# 5x18.net
KiCad netlist of a schematic drawn in EAGLE
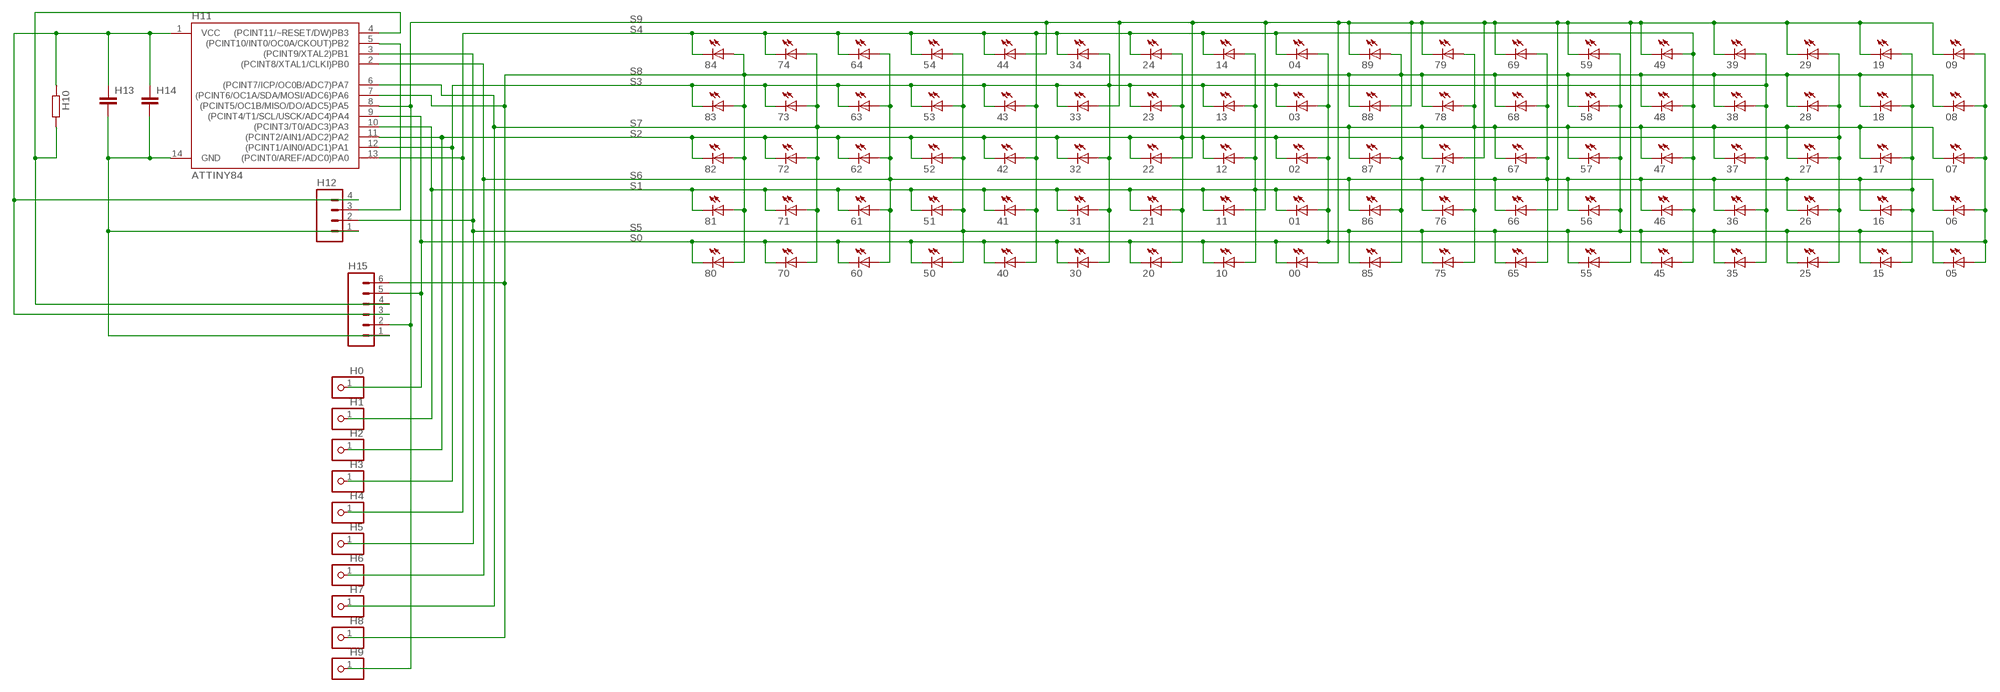
[diagram p0: schematic, sheet 1]

(export (version "E")
  (design (tool "Eeschema 10.0.6"))
  (components
    (comp (ref "00")
      (value "LED3MM")
      (footprint "eagle-import:LED3MM")
      (libsource (lib "eagle-import") (part "LED3MM"))
    )
    (comp (ref "01")
      (value "LED3MM")
      (footprint "eagle-import:LED3MM")
      (libsource (lib "eagle-import") (part "LED3MM"))
    )
    (comp (ref "02")
      (value "LED3MM")
      (footprint "eagle-import:LED3MM")
      (libsource (lib "eagle-import") (part "LED3MM"))
    )
    (comp (ref "03")
      (value "LED3MM")
      (footprint "eagle-import:LED3MM")
      (libsource (lib "eagle-import") (part "LED3MM"))
    )
    (comp (ref "04")
      (value "LED3MM")
      (footprint "eagle-import:LED3MM")
      (libsource (lib "eagle-import") (part "LED3MM"))
    )
    (comp (ref "05")
      (value "LED3MM")
      (footprint "eagle-import:LED3MM")
      (libsource (lib "eagle-import") (part "LED3MM"))
    )
    (comp (ref "06")
      (value "LED3MM")
      (footprint "eagle-import:LED3MM")
      (libsource (lib "eagle-import") (part "LED3MM"))
    )
    (comp (ref "07")
      (value "LED3MM")
      (footprint "eagle-import:LED3MM")
      (libsource (lib "eagle-import") (part "LED3MM"))
    )
    (comp (ref "08")
      (value "LED3MM")
      (footprint "eagle-import:LED3MM")
      (libsource (lib "eagle-import") (part "LED3MM"))
    )
    (comp (ref "09")
      (value "LED3MM")
      (footprint "eagle-import:LED3MM")
      (libsource (lib "eagle-import") (part "LED3MM"))
    )
    (comp (ref "10")
      (value "LED3MM")
      (footprint "eagle-import:LED3MM")
      (libsource (lib "eagle-import") (part "LED3MM"))
    )
    (comp (ref "11")
      (value "LED3MM")
      (footprint "eagle-import:LED3MM")
      (libsource (lib "eagle-import") (part "LED3MM"))
    )
    (comp (ref "12")
      (value "LED3MM")
      (footprint "eagle-import:LED3MM")
      (libsource (lib "eagle-import") (part "LED3MM"))
    )
    (comp (ref "13")
      (value "LED3MM")
      (footprint "eagle-import:LED3MM")
      (libsource (lib "eagle-import") (part "LED3MM"))
    )
    (comp (ref "14")
      (value "LED3MM")
      (footprint "eagle-import:LED3MM")
      (libsource (lib "eagle-import") (part "LED3MM"))
    )
    (comp (ref "15")
      (value "LED3MM")
      (footprint "eagle-import:LED3MM")
      (libsource (lib "eagle-import") (part "LED3MM"))
    )
    (comp (ref "16")
      (value "LED3MM")
      (footprint "eagle-import:LED3MM")
      (libsource (lib "eagle-import") (part "LED3MM"))
    )
    (comp (ref "17")
      (value "LED3MM")
      (footprint "eagle-import:LED3MM")
      (libsource (lib "eagle-import") (part "LED3MM"))
    )
    (comp (ref "18")
      (value "LED3MM")
      (footprint "eagle-import:LED3MM")
      (libsource (lib "eagle-import") (part "LED3MM"))
    )
    (comp (ref "19")
      (value "LED3MM")
      (footprint "eagle-import:LED3MM")
      (libsource (lib "eagle-import") (part "LED3MM"))
    )
    (comp (ref "20")
      (value "LED3MM")
      (footprint "eagle-import:LED3MM")
      (libsource (lib "eagle-import") (part "LED3MM"))
    )
    (comp (ref "21")
      (value "LED3MM")
      (footprint "eagle-import:LED3MM")
      (libsource (lib "eagle-import") (part "LED3MM"))
    )
    (comp (ref "22")
      (value "LED3MM")
      (footprint "eagle-import:LED3MM")
      (libsource (lib "eagle-import") (part "LED3MM"))
    )
    (comp (ref "23")
      (value "LED3MM")
      (footprint "eagle-import:LED3MM")
      (libsource (lib "eagle-import") (part "LED3MM"))
    )
    (comp (ref "24")
      (value "LED3MM")
      (footprint "eagle-import:LED3MM")
      (libsource (lib "eagle-import") (part "LED3MM"))
    )
    (comp (ref "25")
      (value "LED3MM")
      (footprint "eagle-import:LED3MM")
      (libsource (lib "eagle-import") (part "LED3MM"))
    )
    (comp (ref "26")
      (value "LED3MM")
      (footprint "eagle-import:LED3MM")
      (libsource (lib "eagle-import") (part "LED3MM"))
    )
    (comp (ref "27")
      (value "LED3MM")
      (footprint "eagle-import:LED3MM")
      (libsource (lib "eagle-import") (part "LED3MM"))
    )
    (comp (ref "28")
      (value "LED3MM")
      (footprint "eagle-import:LED3MM")
      (libsource (lib "eagle-import") (part "LED3MM"))
    )
    (comp (ref "29")
      (value "LED3MM")
      (footprint "eagle-import:LED3MM")
      (libsource (lib "eagle-import") (part "LED3MM"))
    )
    (comp (ref "30")
      (value "LED3MM")
      (footprint "eagle-import:LED3MM")
      (libsource (lib "eagle-import") (part "LED3MM"))
    )
    (comp (ref "31")
      (value "LED3MM")
      (footprint "eagle-import:LED3MM")
      (libsource (lib "eagle-import") (part "LED3MM"))
    )
    (comp (ref "32")
      (value "LED3MM")
      (footprint "eagle-import:LED3MM")
      (libsource (lib "eagle-import") (part "LED3MM"))
    )
    (comp (ref "33")
      (value "LED3MM")
      (footprint "eagle-import:LED3MM")
      (libsource (lib "eagle-import") (part "LED3MM"))
    )
    (comp (ref "34")
      (value "LED3MM")
      (footprint "eagle-import:LED3MM")
      (libsource (lib "eagle-import") (part "LED3MM"))
    )
    (comp (ref "35")
      (value "LED3MM")
      (footprint "eagle-import:LED3MM")
      (libsource (lib "eagle-import") (part "LED3MM"))
    )
    (comp (ref "36")
      (value "LED3MM")
      (footprint "eagle-import:LED3MM")
      (libsource (lib "eagle-import") (part "LED3MM"))
    )
    (comp (ref "37")
      (value "LED3MM")
      (footprint "eagle-import:LED3MM")
      (libsource (lib "eagle-import") (part "LED3MM"))
    )
    (comp (ref "38")
      (value "LED3MM")
      (footprint "eagle-import:LED3MM")
      (libsource (lib "eagle-import") (part "LED3MM"))
    )
    (comp (ref "39")
      (value "LED3MM")
      (footprint "eagle-import:LED3MM")
      (libsource (lib "eagle-import") (part "LED3MM"))
    )
    (comp (ref "40")
      (value "LED3MM")
      (footprint "eagle-import:LED3MM")
      (libsource (lib "eagle-import") (part "LED3MM"))
    )
    (comp (ref "41")
      (value "LED3MM")
      (footprint "eagle-import:LED3MM")
      (libsource (lib "eagle-import") (part "LED3MM"))
    )
    (comp (ref "42")
      (value "LED3MM")
      (footprint "eagle-import:LED3MM")
      (libsource (lib "eagle-import") (part "LED3MM"))
    )
    (comp (ref "43")
      (value "LED3MM")
      (footprint "eagle-import:LED3MM")
      (libsource (lib "eagle-import") (part "LED3MM"))
    )
    (comp (ref "44")
      (value "LED3MM")
      (footprint "eagle-import:LED3MM")
      (libsource (lib "eagle-import") (part "LED3MM"))
    )
    (comp (ref "45")
      (value "LED3MM")
      (footprint "eagle-import:LED3MM")
      (libsource (lib "eagle-import") (part "LED3MM"))
    )
    (comp (ref "46")
      (value "LED3MM")
      (footprint "eagle-import:LED3MM")
      (libsource (lib "eagle-import") (part "LED3MM"))
    )
    (comp (ref "47")
      (value "LED3MM")
      (footprint "eagle-import:LED3MM")
      (libsource (lib "eagle-import") (part "LED3MM"))
    )
    (comp (ref "48")
      (value "LED3MM")
      (footprint "eagle-import:LED3MM")
      (libsource (lib "eagle-import") (part "LED3MM"))
    )
    (comp (ref "49")
      (value "LED3MM")
      (footprint "eagle-import:LED3MM")
      (libsource (lib "eagle-import") (part "LED3MM"))
    )
    (comp (ref "50")
      (value "LED3MM")
      (footprint "eagle-import:LED3MM")
      (libsource (lib "eagle-import") (part "LED3MM"))
    )
    (comp (ref "51")
      (value "LED3MM")
      (footprint "eagle-import:LED3MM")
      (libsource (lib "eagle-import") (part "LED3MM"))
    )
    (comp (ref "52")
      (value "LED3MM")
      (footprint "eagle-import:LED3MM")
      (libsource (lib "eagle-import") (part "LED3MM"))
    )
    (comp (ref "53")
      (value "LED3MM")
      (footprint "eagle-import:LED3MM")
      (libsource (lib "eagle-import") (part "LED3MM"))
    )
    (comp (ref "54")
      (value "LED3MM")
      (footprint "eagle-import:LED3MM")
      (libsource (lib "eagle-import") (part "LED3MM"))
    )
    (comp (ref "55")
      (value "LED3MM")
      (footprint "eagle-import:LED3MM")
      (libsource (lib "eagle-import") (part "LED3MM"))
    )
    (comp (ref "56")
      (value "LED3MM")
      (footprint "eagle-import:LED3MM")
      (libsource (lib "eagle-import") (part "LED3MM"))
    )
    (comp (ref "57")
      (value "LED3MM")
      (footprint "eagle-import:LED3MM")
      (libsource (lib "eagle-import") (part "LED3MM"))
    )
    (comp (ref "58")
      (value "LED3MM")
      (footprint "eagle-import:LED3MM")
      (libsource (lib "eagle-import") (part "LED3MM"))
    )
    (comp (ref "59")
      (value "LED3MM")
      (footprint "eagle-import:LED3MM")
      (libsource (lib "eagle-import") (part "LED3MM"))
    )
    (comp (ref "60")
      (value "LED3MM")
      (footprint "eagle-import:LED3MM")
      (libsource (lib "eagle-import") (part "LED3MM"))
    )
    (comp (ref "61")
      (value "LED3MM")
      (footprint "eagle-import:LED3MM")
      (libsource (lib "eagle-import") (part "LED3MM"))
    )
    (comp (ref "62")
      (value "LED3MM")
      (footprint "eagle-import:LED3MM")
      (libsource (lib "eagle-import") (part "LED3MM"))
    )
    (comp (ref "63")
      (value "LED3MM")
      (footprint "eagle-import:LED3MM")
      (libsource (lib "eagle-import") (part "LED3MM"))
    )
    (comp (ref "64")
      (value "LED3MM")
      (footprint "eagle-import:LED3MM")
      (libsource (lib "eagle-import") (part "LED3MM"))
    )
    (comp (ref "65")
      (value "LED3MM")
      (footprint "eagle-import:LED3MM")
      (libsource (lib "eagle-import") (part "LED3MM"))
    )
    (comp (ref "66")
      (value "LED3MM")
      (footprint "eagle-import:LED3MM")
      (libsource (lib "eagle-import") (part "LED3MM"))
    )
    (comp (ref "67")
      (value "LED3MM")
      (footprint "eagle-import:LED3MM")
      (libsource (lib "eagle-import") (part "LED3MM"))
    )
    (comp (ref "68")
      (value "LED3MM")
      (footprint "eagle-import:LED3MM")
      (libsource (lib "eagle-import") (part "LED3MM"))
    )
    (comp (ref "69")
      (value "LED3MM")
      (footprint "eagle-import:LED3MM")
      (libsource (lib "eagle-import") (part "LED3MM"))
    )
    (comp (ref "70")
      (value "LED3MM")
      (footprint "eagle-import:LED3MM")
      (libsource (lib "eagle-import") (part "LED3MM"))
    )
    (comp (ref "71")
      (value "LED3MM")
      (footprint "eagle-import:LED3MM")
      (libsource (lib "eagle-import") (part "LED3MM"))
    )
    (comp (ref "72")
      (value "LED3MM")
      (footprint "eagle-import:LED3MM")
      (libsource (lib "eagle-import") (part "LED3MM"))
    )
    (comp (ref "73")
      (value "LED3MM")
      (footprint "eagle-import:LED3MM")
      (libsource (lib "eagle-import") (part "LED3MM"))
    )
    (comp (ref "74")
      (value "LED3MM")
      (footprint "eagle-import:LED3MM")
      (libsource (lib "eagle-import") (part "LED3MM"))
    )
    (comp (ref "75")
      (value "LED3MM")
      (footprint "eagle-import:LED3MM")
      (libsource (lib "eagle-import") (part "LED3MM"))
    )
    (comp (ref "76")
      (value "LED3MM")
      (footprint "eagle-import:LED3MM")
      (libsource (lib "eagle-import") (part "LED3MM"))
    )
    (comp (ref "77")
      (value "LED3MM")
      (footprint "eagle-import:LED3MM")
      (libsource (lib "eagle-import") (part "LED3MM"))
    )
    (comp (ref "78")
      (value "LED3MM")
      (footprint "eagle-import:LED3MM")
      (libsource (lib "eagle-import") (part "LED3MM"))
    )
    (comp (ref "79")
      (value "LED3MM")
      (footprint "eagle-import:LED3MM")
      (libsource (lib "eagle-import") (part "LED3MM"))
    )
    (comp (ref "80")
      (value "LED3MM")
      (footprint "eagle-import:LED3MM")
      (libsource (lib "eagle-import") (part "LED3MM"))
    )
    (comp (ref "81")
      (value "LED3MM")
      (footprint "eagle-import:LED3MM")
      (libsource (lib "eagle-import") (part "LED3MM"))
    )
    (comp (ref "82")
      (value "LED3MM")
      (footprint "eagle-import:LED3MM")
      (libsource (lib "eagle-import") (part "LED3MM"))
    )
    (comp (ref "83")
      (value "LED3MM")
      (footprint "eagle-import:LED3MM")
      (libsource (lib "eagle-import") (part "LED3MM"))
    )
    (comp (ref "84")
      (value "LED3MM")
      (footprint "eagle-import:LED3MM")
      (libsource (lib "eagle-import") (part "LED3MM"))
    )
    (comp (ref "85")
      (value "LED3MM")
      (footprint "eagle-import:LED3MM")
      (libsource (lib "eagle-import") (part "LED3MM"))
    )
    (comp (ref "86")
      (value "LED3MM")
      (footprint "eagle-import:LED3MM")
      (libsource (lib "eagle-import") (part "LED3MM"))
    )
    (comp (ref "87")
      (value "LED3MM")
      (footprint "eagle-import:LED3MM")
      (libsource (lib "eagle-import") (part "LED3MM"))
    )
    (comp (ref "88")
      (value "LED3MM")
      (footprint "eagle-import:LED3MM")
      (libsource (lib "eagle-import") (part "LED3MM"))
    )
    (comp (ref "89")
      (value "LED3MM")
      (footprint "eagle-import:LED3MM")
      (libsource (lib "eagle-import") (part "LED3MM"))
    )
    (comp (ref "H0")
      (value "PINHD-1X1")
      (footprint "eagle-import:1X01")
      (libsource (lib "eagle-import") (part "PINHD-1X1"))
    )
    (comp (ref "H1")
      (value "PINHD-1X1")
      (footprint "eagle-import:1X01")
      (libsource (lib "eagle-import") (part "PINHD-1X1"))
    )
    (comp (ref "H2")
      (value "PINHD-1X1")
      (footprint "eagle-import:1X01")
      (libsource (lib "eagle-import") (part "PINHD-1X1"))
    )
    (comp (ref "H3")
      (value "PINHD-1X1")
      (footprint "eagle-import:1X01")
      (libsource (lib "eagle-import") (part "PINHD-1X1"))
    )
    (comp (ref "H4")
      (value "PINHD-1X1")
      (footprint "eagle-import:1X01")
      (libsource (lib "eagle-import") (part "PINHD-1X1"))
    )
    (comp (ref "H5")
      (value "PINHD-1X1")
      (footprint "eagle-import:1X01")
      (libsource (lib "eagle-import") (part "PINHD-1X1"))
    )
    (comp (ref "H6")
      (value "PINHD-1X1")
      (footprint "eagle-import:1X01")
      (libsource (lib "eagle-import") (part "PINHD-1X1"))
    )
    (comp (ref "H7")
      (value "PINHD-1X1")
      (footprint "eagle-import:1X01")
      (libsource (lib "eagle-import") (part "PINHD-1X1"))
    )
    (comp (ref "H8")
      (value "PINHD-1X1")
      (footprint "eagle-import:1X01")
      (libsource (lib "eagle-import") (part "PINHD-1X1"))
    )
    (comp (ref "H9")
      (value "PINHD-1X1")
      (footprint "eagle-import:1X01")
      (libsource (lib "eagle-import") (part "PINHD-1X1"))
    )
    (comp (ref "H10")
      (value "R-EU_0204/7")
      (footprint "eagle-import:0204_7")
      (libsource (lib "eagle-import") (part "R-EU_0204/7"))
    )
    (comp (ref "H11")
      (value "ATTINY84")
      (footprint "eagle-import:SO14")
      (libsource (lib "eagle-import") (part "ATTINY84"))
    )
    (comp (ref "H12")
      (value "M04LOCK")
      (footprint "eagle-import:1X04_LOCK")
      (libsource (lib "eagle-import") (part "M04LOCK"))
    )
    (comp (ref "H13")
      (value "C-EU050-025X075")
      (footprint "eagle-import:C050-025X075")
      (libsource (lib "eagle-import") (part "C-EU050-025X075"))
    )
    (comp (ref "H14")
      (value "C-EU050-025X075")
      (footprint "eagle-import:C050-025X075")
      (libsource (lib "eagle-import") (part "C-EU050-025X075"))
    )
    (comp (ref "H15")
      (value "M06LOCK")
      (footprint "eagle-import:1X06_LOCK")
      (libsource (lib "eagle-import") (part "M06LOCK"))
    )
  )
  (nets
    (net (code "1") (name "/S0") (class "Default")
      (node (ref "00") (pin "K") (pinfunction "C_K") (pintype "passive"))
      (node (ref "01") (pin "A") (pinfunction "A_A") (pintype "passive"))
      (node (ref "02") (pin "A") (pinfunction "A_A") (pintype "passive"))
      (node (ref "03") (pin "A") (pinfunction "A_A") (pintype "passive"))
      (node (ref "04") (pin "A") (pinfunction "A_A") (pintype "passive"))
      (node (ref "05") (pin "A") (pinfunction "A_A") (pintype "passive"))
      (node (ref "06") (pin "A") (pinfunction "A_A") (pintype "passive"))
      (node (ref "07") (pin "A") (pinfunction "A_A") (pintype "passive"))
      (node (ref "08") (pin "A") (pinfunction "A_A") (pintype "passive"))
      (node (ref "09") (pin "A") (pinfunction "A_A") (pintype "passive"))
      (node (ref "10") (pin "K") (pinfunction "C_K") (pintype "passive"))
      (node (ref "20") (pin "K") (pinfunction "C_K") (pintype "passive"))
      (node (ref "30") (pin "K") (pinfunction "C_K") (pintype "passive"))
      (node (ref "40") (pin "K") (pinfunction "C_K") (pintype "passive"))
      (node (ref "50") (pin "K") (pinfunction "C_K") (pintype "passive"))
      (node (ref "60") (pin "K") (pinfunction "C_K") (pintype "passive"))
      (node (ref "70") (pin "K") (pinfunction "C_K") (pintype "passive"))
      (node (ref "80") (pin "K") (pinfunction "C_K") (pintype "passive"))
      (node (ref "H0") (pin "1") (pinfunction "1_1") (pintype "passive"))
      (node (ref "H11") (pin "9") (pinfunction "(PCINT4/T1/SCL/USCK/ADC4)PA4_9") (pintype "bidirectional"))
      (node (ref "H15") (pin "5") (pinfunction "5_5") (pintype "passive"))
    )
    (net (code "2") (name "/S1") (class "Default")
      (node (ref "01") (pin "K") (pinfunction "C_K") (pintype "passive"))
      (node (ref "10") (pin "A") (pinfunction "A_A") (pintype "passive"))
      (node (ref "11") (pin "K") (pinfunction "C_K") (pintype "passive"))
      (node (ref "12") (pin "A") (pinfunction "A_A") (pintype "passive"))
      (node (ref "13") (pin "A") (pinfunction "A_A") (pintype "passive"))
      (node (ref "14") (pin "A") (pinfunction "A_A") (pintype "passive"))
      (node (ref "15") (pin "A") (pinfunction "A_A") (pintype "passive"))
      (node (ref "16") (pin "A") (pinfunction "A_A") (pintype "passive"))
      (node (ref "17") (pin "A") (pinfunction "A_A") (pintype "passive"))
      (node (ref "18") (pin "A") (pinfunction "A_A") (pintype "passive"))
      (node (ref "19") (pin "A") (pinfunction "A_A") (pintype "passive"))
      (node (ref "21") (pin "K") (pinfunction "C_K") (pintype "passive"))
      (node (ref "31") (pin "K") (pinfunction "C_K") (pintype "passive"))
      (node (ref "41") (pin "K") (pinfunction "C_K") (pintype "passive"))
      (node (ref "51") (pin "K") (pinfunction "C_K") (pintype "passive"))
      (node (ref "61") (pin "K") (pinfunction "C_K") (pintype "passive"))
      (node (ref "71") (pin "K") (pinfunction "C_K") (pintype "passive"))
      (node (ref "81") (pin "K") (pinfunction "C_K") (pintype "passive"))
      (node (ref "H1") (pin "1") (pinfunction "1_1") (pintype "passive"))
      (node (ref "H11") (pin "10") (pinfunction "(PCINT3/T0/ADC3)PA3_10") (pintype "bidirectional"))
    )
    (net (code "3") (name "/S2") (class "Default")
      (node (ref "02") (pin "K") (pinfunction "C_K") (pintype "passive"))
      (node (ref "12") (pin "K") (pinfunction "C_K") (pintype "passive"))
      (node (ref "20") (pin "A") (pinfunction "A_A") (pintype "passive"))
      (node (ref "21") (pin "A") (pinfunction "A_A") (pintype "passive"))
      (node (ref "22") (pin "K") (pinfunction "C_K") (pintype "passive"))
      (node (ref "23") (pin "A") (pinfunction "A_A") (pintype "passive"))
      (node (ref "24") (pin "A") (pinfunction "A_A") (pintype "passive"))
      (node (ref "25") (pin "A") (pinfunction "A_A") (pintype "passive"))
      (node (ref "26") (pin "A") (pinfunction "A_A") (pintype "passive"))
      (node (ref "27") (pin "A") (pinfunction "A_A") (pintype "passive"))
      (node (ref "28") (pin "A") (pinfunction "A_A") (pintype "passive"))
      (node (ref "29") (pin "A") (pinfunction "A_A") (pintype "passive"))
      (node (ref "32") (pin "K") (pinfunction "C_K") (pintype "passive"))
      (node (ref "42") (pin "K") (pinfunction "C_K") (pintype "passive"))
      (node (ref "52") (pin "K") (pinfunction "C_K") (pintype "passive"))
      (node (ref "62") (pin "K") (pinfunction "C_K") (pintype "passive"))
      (node (ref "72") (pin "K") (pinfunction "C_K") (pintype "passive"))
      (node (ref "82") (pin "K") (pinfunction "C_K") (pintype "passive"))
      (node (ref "H11") (pin "11") (pinfunction "(PCINT2/AIN1/ADC2)PA2_11") (pintype "bidirectional"))
      (node (ref "H2") (pin "1") (pinfunction "1_1") (pintype "passive"))
    )
    (net (code "4") (name "/S3") (class "Default")
      (node (ref "03") (pin "K") (pinfunction "C_K") (pintype "passive"))
      (node (ref "13") (pin "K") (pinfunction "C_K") (pintype "passive"))
      (node (ref "23") (pin "K") (pinfunction "C_K") (pintype "passive"))
      (node (ref "30") (pin "A") (pinfunction "A_A") (pintype "passive"))
      (node (ref "31") (pin "A") (pinfunction "A_A") (pintype "passive"))
      (node (ref "32") (pin "A") (pinfunction "A_A") (pintype "passive"))
      (node (ref "33") (pin "K") (pinfunction "C_K") (pintype "passive"))
      (node (ref "34") (pin "A") (pinfunction "A_A") (pintype "passive"))
      (node (ref "35") (pin "A") (pinfunction "A_A") (pintype "passive"))
      (node (ref "36") (pin "A") (pinfunction "A_A") (pintype "passive"))
      (node (ref "37") (pin "A") (pinfunction "A_A") (pintype "passive"))
      (node (ref "38") (pin "A") (pinfunction "A_A") (pintype "passive"))
      (node (ref "39") (pin "A") (pinfunction "A_A") (pintype "passive"))
      (node (ref "43") (pin "K") (pinfunction "C_K") (pintype "passive"))
      (node (ref "53") (pin "K") (pinfunction "C_K") (pintype "passive"))
      (node (ref "63") (pin "K") (pinfunction "C_K") (pintype "passive"))
      (node (ref "73") (pin "K") (pinfunction "C_K") (pintype "passive"))
      (node (ref "83") (pin "K") (pinfunction "C_K") (pintype "passive"))
      (node (ref "H11") (pin "12") (pinfunction "(PCINT1/AIN0/ADC1)PA1_12") (pintype "bidirectional"))
      (node (ref "H3") (pin "1") (pinfunction "1_1") (pintype "passive"))
    )
    (net (code "5") (name "/S4") (class "Default")
      (node (ref "04") (pin "K") (pinfunction "C_K") (pintype "passive"))
      (node (ref "14") (pin "K") (pinfunction "C_K") (pintype "passive"))
      (node (ref "24") (pin "K") (pinfunction "C_K") (pintype "passive"))
      (node (ref "34") (pin "K") (pinfunction "C_K") (pintype "passive"))
      (node (ref "40") (pin "A") (pinfunction "A_A") (pintype "passive"))
      (node (ref "41") (pin "A") (pinfunction "A_A") (pintype "passive"))
      (node (ref "42") (pin "A") (pinfunction "A_A") (pintype "passive"))
      (node (ref "43") (pin "A") (pinfunction "A_A") (pintype "passive"))
      (node (ref "44") (pin "K") (pinfunction "C_K") (pintype "passive"))
      (node (ref "45") (pin "A") (pinfunction "A_A") (pintype "passive"))
      (node (ref "46") (pin "A") (pinfunction "A_A") (pintype "passive"))
      (node (ref "47") (pin "A") (pinfunction "A_A") (pintype "passive"))
      (node (ref "48") (pin "A") (pinfunction "A_A") (pintype "passive"))
      (node (ref "49") (pin "A") (pinfunction "A_A") (pintype "passive"))
      (node (ref "54") (pin "K") (pinfunction "C_K") (pintype "passive"))
      (node (ref "64") (pin "K") (pinfunction "C_K") (pintype "passive"))
      (node (ref "74") (pin "K") (pinfunction "C_K") (pintype "passive"))
      (node (ref "84") (pin "K") (pinfunction "C_K") (pintype "passive"))
      (node (ref "H11") (pin "13") (pinfunction "(PCINT0/AREF/ADC0)PA0_13") (pintype "bidirectional"))
      (node (ref "H4") (pin "1") (pinfunction "1_1") (pintype "passive"))
    )
    (net (code "6") (name "/S5") (class "Default")
      (node (ref "05") (pin "K") (pinfunction "C_K") (pintype "passive"))
      (node (ref "15") (pin "K") (pinfunction "C_K") (pintype "passive"))
      (node (ref "25") (pin "K") (pinfunction "C_K") (pintype "passive"))
      (node (ref "35") (pin "K") (pinfunction "C_K") (pintype "passive"))
      (node (ref "45") (pin "K") (pinfunction "C_K") (pintype "passive"))
      (node (ref "50") (pin "A") (pinfunction "A_A") (pintype "passive"))
      (node (ref "51") (pin "A") (pinfunction "A_A") (pintype "passive"))
      (node (ref "52") (pin "A") (pinfunction "A_A") (pintype "passive"))
      (node (ref "53") (pin "A") (pinfunction "A_A") (pintype "passive"))
      (node (ref "54") (pin "A") (pinfunction "A_A") (pintype "passive"))
      (node (ref "55") (pin "K") (pinfunction "C_K") (pintype "passive"))
      (node (ref "56") (pin "A") (pinfunction "A_A") (pintype "passive"))
      (node (ref "57") (pin "A") (pinfunction "A_A") (pintype "passive"))
      (node (ref "58") (pin "A") (pinfunction "A_A") (pintype "passive"))
      (node (ref "59") (pin "A") (pinfunction "A_A") (pintype "passive"))
      (node (ref "65") (pin "K") (pinfunction "C_K") (pintype "passive"))
      (node (ref "75") (pin "K") (pinfunction "C_K") (pintype "passive"))
      (node (ref "85") (pin "K") (pinfunction "C_K") (pintype "passive"))
      (node (ref "H11") (pin "3") (pinfunction "(PCINT9/XTAL2)PB1_3") (pintype "bidirectional"))
      (node (ref "H12") (pin "2") (pinfunction "2_2") (pintype "passive"))
      (node (ref "H5") (pin "1") (pinfunction "1_1") (pintype "passive"))
    )
    (net (code "7") (name "/S6") (class "Default")
      (node (ref "06") (pin "K") (pinfunction "C_K") (pintype "passive"))
      (node (ref "16") (pin "K") (pinfunction "C_K") (pintype "passive"))
      (node (ref "26") (pin "K") (pinfunction "C_K") (pintype "passive"))
      (node (ref "36") (pin "K") (pinfunction "C_K") (pintype "passive"))
      (node (ref "46") (pin "K") (pinfunction "C_K") (pintype "passive"))
      (node (ref "56") (pin "K") (pinfunction "C_K") (pintype "passive"))
      (node (ref "60") (pin "A") (pinfunction "A_A") (pintype "passive"))
      (node (ref "61") (pin "A") (pinfunction "A_A") (pintype "passive"))
      (node (ref "62") (pin "A") (pinfunction "A_A") (pintype "passive"))
      (node (ref "63") (pin "A") (pinfunction "A_A") (pintype "passive"))
      (node (ref "64") (pin "A") (pinfunction "A_A") (pintype "passive"))
      (node (ref "65") (pin "A") (pinfunction "A_A") (pintype "passive"))
      (node (ref "66") (pin "K") (pinfunction "C_K") (pintype "passive"))
      (node (ref "67") (pin "A") (pinfunction "A_A") (pintype "passive"))
      (node (ref "68") (pin "A") (pinfunction "A_A") (pintype "passive"))
      (node (ref "69") (pin "A") (pinfunction "A_A") (pintype "passive"))
      (node (ref "76") (pin "K") (pinfunction "C_K") (pintype "passive"))
      (node (ref "86") (pin "K") (pinfunction "C_K") (pintype "passive"))
      (node (ref "H11") (pin "2") (pinfunction "(PCINT8/XTAL1/CLKI)PB0_2") (pintype "bidirectional"))
      (node (ref "H6") (pin "1") (pinfunction "1_1") (pintype "passive"))
    )
    (net (code "8") (name "/S7") (class "Default")
      (node (ref "07") (pin "K") (pinfunction "C_K") (pintype "passive"))
      (node (ref "17") (pin "K") (pinfunction "C_K") (pintype "passive"))
      (node (ref "27") (pin "K") (pinfunction "C_K") (pintype "passive"))
      (node (ref "37") (pin "K") (pinfunction "C_K") (pintype "passive"))
      (node (ref "47") (pin "K") (pinfunction "C_K") (pintype "passive"))
      (node (ref "57") (pin "K") (pinfunction "C_K") (pintype "passive"))
      (node (ref "67") (pin "K") (pinfunction "C_K") (pintype "passive"))
      (node (ref "70") (pin "A") (pinfunction "A_A") (pintype "passive"))
      (node (ref "71") (pin "A") (pinfunction "A_A") (pintype "passive"))
      (node (ref "72") (pin "A") (pinfunction "A_A") (pintype "passive"))
      (node (ref "73") (pin "A") (pinfunction "A_A") (pintype "passive"))
      (node (ref "74") (pin "A") (pinfunction "A_A") (pintype "passive"))
      (node (ref "75") (pin "A") (pinfunction "A_A") (pintype "passive"))
      (node (ref "76") (pin "A") (pinfunction "A_A") (pintype "passive"))
      (node (ref "77") (pin "K") (pinfunction "C_K") (pintype "passive"))
      (node (ref "78") (pin "A") (pinfunction "A_A") (pintype "passive"))
      (node (ref "79") (pin "A") (pinfunction "A_A") (pintype "passive"))
      (node (ref "87") (pin "K") (pinfunction "C_K") (pintype "passive"))
      (node (ref "H11") (pin "6") (pinfunction "(PCINT7/ICP/OC0B/ADC7)PA7_6") (pintype "bidirectional"))
      (node (ref "H7") (pin "1") (pinfunction "1_1") (pintype "passive"))
    )
    (net (code "9") (name "/S8") (class "Default")
      (node (ref "08") (pin "K") (pinfunction "C_K") (pintype "passive"))
      (node (ref "18") (pin "K") (pinfunction "C_K") (pintype "passive"))
      (node (ref "28") (pin "K") (pinfunction "C_K") (pintype "passive"))
      (node (ref "38") (pin "K") (pinfunction "C_K") (pintype "passive"))
      (node (ref "48") (pin "K") (pinfunction "C_K") (pintype "passive"))
      (node (ref "58") (pin "K") (pinfunction "C_K") (pintype "passive"))
      (node (ref "68") (pin "K") (pinfunction "C_K") (pintype "passive"))
      (node (ref "78") (pin "K") (pinfunction "C_K") (pintype "passive"))
      (node (ref "80") (pin "A") (pinfunction "A_A") (pintype "passive"))
      (node (ref "81") (pin "A") (pinfunction "A_A") (pintype "passive"))
      (node (ref "82") (pin "A") (pinfunction "A_A") (pintype "passive"))
      (node (ref "83") (pin "A") (pinfunction "A_A") (pintype "passive"))
      (node (ref "84") (pin "A") (pinfunction "A_A") (pintype "passive"))
      (node (ref "85") (pin "A") (pinfunction "A_A") (pintype "passive"))
      (node (ref "86") (pin "A") (pinfunction "A_A") (pintype "passive"))
      (node (ref "87") (pin "A") (pinfunction "A_A") (pintype "passive"))
      (node (ref "88") (pin "K") (pinfunction "C_K") (pintype "passive"))
      (node (ref "89") (pin "A") (pinfunction "A_A") (pintype "passive"))
      (node (ref "H11") (pin "7") (pinfunction "(PCINT6/OC1A/SDA/MOSI/ADC6)PA6_7") (pintype "bidirectional"))
      (node (ref "H15") (pin "6") (pinfunction "6_6") (pintype "passive"))
      (node (ref "H8") (pin "1") (pinfunction "1_1") (pintype "passive"))
    )
    (net (code "10") (name "/S9") (class "Default")
      (node (ref "00") (pin "A") (pinfunction "A_A") (pintype "passive"))
      (node (ref "09") (pin "K") (pinfunction "C_K") (pintype "passive"))
      (node (ref "11") (pin "A") (pinfunction "A_A") (pintype "passive"))
      (node (ref "19") (pin "K") (pinfunction "C_K") (pintype "passive"))
      (node (ref "22") (pin "A") (pinfunction "A_A") (pintype "passive"))
      (node (ref "29") (pin "K") (pinfunction "C_K") (pintype "passive"))
      (node (ref "33") (pin "A") (pinfunction "A_A") (pintype "passive"))
      (node (ref "39") (pin "K") (pinfunction "C_K") (pintype "passive"))
      (node (ref "44") (pin "A") (pinfunction "A_A") (pintype "passive"))
      (node (ref "49") (pin "K") (pinfunction "C_K") (pintype "passive"))
      (node (ref "55") (pin "A") (pinfunction "A_A") (pintype "passive"))
      (node (ref "59") (pin "K") (pinfunction "C_K") (pintype "passive"))
      (node (ref "66") (pin "A") (pinfunction "A_A") (pintype "passive"))
      (node (ref "69") (pin "K") (pinfunction "C_K") (pintype "passive"))
      (node (ref "77") (pin "A") (pinfunction "A_A") (pintype "passive"))
      (node (ref "79") (pin "K") (pinfunction "C_K") (pintype "passive"))
      (node (ref "88") (pin "A") (pinfunction "A_A") (pintype "passive"))
      (node (ref "89") (pin "K") (pinfunction "C_K") (pintype "passive"))
      (node (ref "H11") (pin "8") (pinfunction "(PCINT5/OC1B/MISO/DO/ADC5)PA5_8") (pintype "bidirectional"))
      (node (ref "H15") (pin "2") (pinfunction "2_2") (pintype "passive"))
      (node (ref "H9") (pin "1") (pinfunction "1_1") (pintype "passive"))
    )
    (net (code "11") (name "Net-(H11-(PCINT10{slash}INT0{slash}OC0A{slash}CKOUT)PB2)") (class "Default")
      (node (ref "H11") (pin "5") (pinfunction "(PCINT10/INT0/OC0A/CKOUT)PB2_5") (pintype "bidirectional"))
      (node (ref "H12") (pin "3") (pinfunction "3_3") (pintype "passive"))
    )
    (net (code "12") (name "Net-(H11-(PCINT11{slash}~{RESET{slash}DW})PB3)") (class "Default")
      (node (ref "H10") (pin "2") (pinfunction "2_2") (pintype "passive"))
      (node (ref "H11") (pin "4") (pinfunction "(PCINT11/~{RESET/DW})PB3_4") (pintype "bidirectional"))
      (node (ref "H15") (pin "4") (pinfunction "4_4") (pintype "passive"))
    )
    (net (code "13") (name "Net-(H11-GND)") (class "Default")
      (node (ref "H11") (pin "14") (pinfunction "GND_14") (pintype "bidirectional"))
      (node (ref "H12") (pin "1") (pinfunction "1_1") (pintype "passive"))
      (node (ref "H13") (pin "2") (pinfunction "2_2") (pintype "passive"))
      (node (ref "H14") (pin "2") (pinfunction "2_2") (pintype "passive"))
      (node (ref "H15") (pin "1") (pinfunction "1_1") (pintype "passive"))
    )
    (net (code "14") (name "Net-(H11-VCC)") (class "Default")
      (node (ref "H10") (pin "1") (pinfunction "1_1") (pintype "passive"))
      (node (ref "H11") (pin "1") (pinfunction "VCC_1") (pintype "bidirectional"))
      (node (ref "H12") (pin "4") (pinfunction "4_4") (pintype "passive"))
      (node (ref "H13") (pin "1") (pinfunction "1_1") (pintype "passive"))
      (node (ref "H14") (pin "1") (pinfunction "1_1") (pintype "passive"))
      (node (ref "H15") (pin "3") (pinfunction "3_3") (pintype "passive"))
    )
  )
)
